# pcb-covox.net
KiCad netlist of a schematic drawn in EAGLE
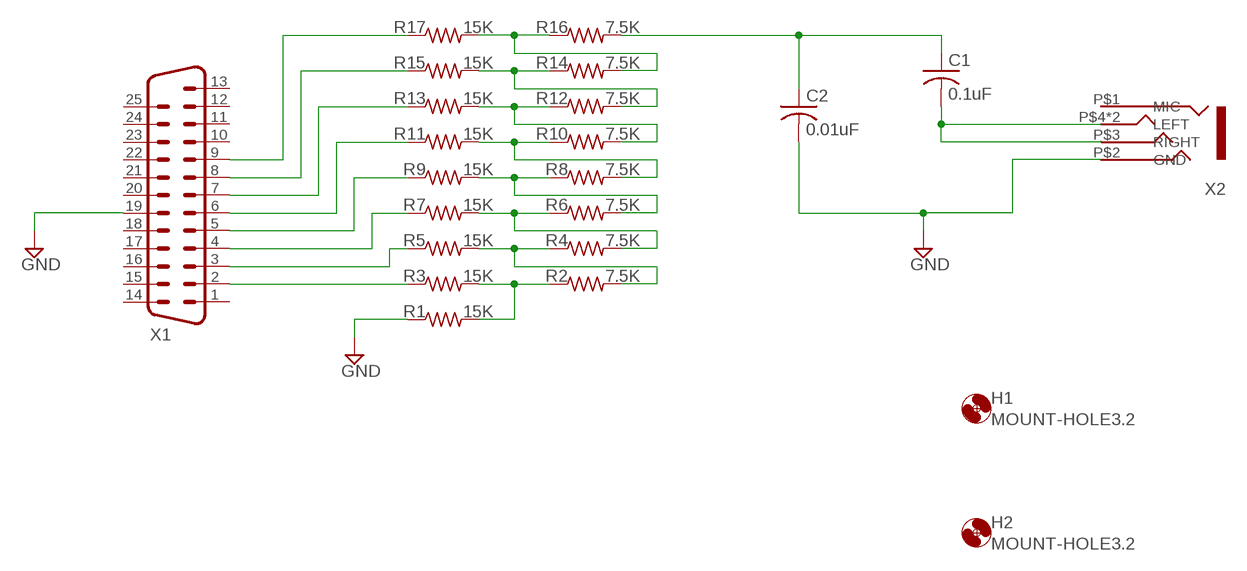
[diagram p0: schematic, sheet 1]

(export (version "E")
  (design (tool "Eeschema 10.0.6"))
  (components
    (comp (ref "C1")
      (value "0.1uF")
      (footprint "eagle-import:C0805")
      (libsource (lib "eagle-import") (part "C-USC0805"))
    )
    (comp (ref "C2")
      (value "0.01uF")
      (footprint "eagle-import:C0805")
      (libsource (lib "eagle-import") (part "C-USC0805"))
    )
    (comp (ref "H1")
      (value "MOUNT-HOLE3.2")
      (footprint "eagle-import:3,2")
      (libsource (lib "eagle-import") (part "MOUNT-HOLE3.2"))
    )
    (comp (ref "H2")
      (value "MOUNT-HOLE3.2")
      (footprint "eagle-import:3,2")
      (libsource (lib "eagle-import") (part "MOUNT-HOLE3.2"))
    )
    (comp (ref "R1")
      (value "15K")
      (footprint "eagle-import:R0805")
      (libsource (lib "eagle-import") (part "R-US_R0805"))
    )
    (comp (ref "R2")
      (value "7.5K")
      (footprint "eagle-import:R0805")
      (libsource (lib "eagle-import") (part "R-US_R0805"))
    )
    (comp (ref "R3")
      (value "15K")
      (footprint "eagle-import:R0805")
      (libsource (lib "eagle-import") (part "R-US_R0805"))
    )
    (comp (ref "R4")
      (value "7.5K")
      (footprint "eagle-import:R0805")
      (libsource (lib "eagle-import") (part "R-US_R0805"))
    )
    (comp (ref "R5")
      (value "15K")
      (footprint "eagle-import:R0805")
      (libsource (lib "eagle-import") (part "R-US_R0805"))
    )
    (comp (ref "R6")
      (value "7.5K")
      (footprint "eagle-import:R0805")
      (libsource (lib "eagle-import") (part "R-US_R0805"))
    )
    (comp (ref "R7")
      (value "15K")
      (footprint "eagle-import:R0805")
      (libsource (lib "eagle-import") (part "R-US_R0805"))
    )
    (comp (ref "R8")
      (value "7.5K")
      (footprint "eagle-import:R0805")
      (libsource (lib "eagle-import") (part "R-US_R0805"))
    )
    (comp (ref "R9")
      (value "15K")
      (footprint "eagle-import:R0805")
      (libsource (lib "eagle-import") (part "R-US_R0805"))
    )
    (comp (ref "R10")
      (value "7.5K")
      (footprint "eagle-import:R0805")
      (libsource (lib "eagle-import") (part "R-US_R0805"))
    )
    (comp (ref "R11")
      (value "15K")
      (footprint "eagle-import:R0805")
      (libsource (lib "eagle-import") (part "R-US_R0805"))
    )
    (comp (ref "R12")
      (value "7.5K")
      (footprint "eagle-import:R0805")
      (libsource (lib "eagle-import") (part "R-US_R0805"))
    )
    (comp (ref "R13")
      (value "15K")
      (footprint "eagle-import:R0805")
      (libsource (lib "eagle-import") (part "R-US_R0805"))
    )
    (comp (ref "R14")
      (value "7.5K")
      (footprint "eagle-import:R0805")
      (libsource (lib "eagle-import") (part "R-US_R0805"))
    )
    (comp (ref "R15")
      (value "15K")
      (footprint "eagle-import:R0805")
      (libsource (lib "eagle-import") (part "R-US_R0805"))
    )
    (comp (ref "R16")
      (value "7.5K")
      (footprint "eagle-import:R0805")
      (libsource (lib "eagle-import") (part "R-US_R0805"))
    )
    (comp (ref "R17")
      (value "15K")
      (footprint "eagle-import:R0805")
      (libsource (lib "eagle-import") (part "R-US_R0805"))
    )
    (comp (ref "X1")
      (value "M25HP")
      (footprint "eagle-import:M25HP")
      (libsource (lib "eagle-import") (part "M25HP"))
    )
    (comp (ref "X2")
      (value "MJ-2135MJ-2135")
      (footprint "eagle-import:MJ-2135")
      (libsource (lib "eagle-import") (part "MJ-2135MJ-2135"))
    )
  )
  (nets
    (net (code "1") (name "GND") (class "Default")
      (node (ref "C2") (pin "2") (pinfunction "2_2") (pintype "passive"))
      (node (ref "R1") (pin "1") (pinfunction "1_1") (pintype "passive"))
      (node (ref "X1") (pin "19") (pinfunction "19_19") (pintype "passive"))
      (node (ref "X2") (pin "P$2") (pinfunction "GND_P$2") (pintype "bidirectional"))
    )
    (net (code "2") (name "Net-(C1-Pad1)") (class "Default")
      (node (ref "C1") (pin "1") (pinfunction "1_1") (pintype "passive"))
      (node (ref "C2") (pin "1") (pinfunction "1_1") (pintype "passive"))
      (node (ref "R16") (pin "2") (pinfunction "2_2") (pintype "passive"))
    )
    (net (code "3") (name "Net-(R1-Pad2)") (class "Default")
      (node (ref "R1") (pin "2") (pinfunction "2_2") (pintype "passive"))
      (node (ref "R2") (pin "1") (pinfunction "1_1") (pintype "passive"))
      (node (ref "R3") (pin "2") (pinfunction "2_2") (pintype "passive"))
    )
    (net (code "4") (name "Net-(R2-Pad2)") (class "Default")
      (node (ref "R2") (pin "2") (pinfunction "2_2") (pintype "passive"))
      (node (ref "R4") (pin "1") (pinfunction "1_1") (pintype "passive"))
      (node (ref "R5") (pin "2") (pinfunction "2_2") (pintype "passive"))
    )
    (net (code "5") (name "Net-(R3-Pad1)") (class "Default")
      (node (ref "R3") (pin "1") (pinfunction "1_1") (pintype "passive"))
      (node (ref "X1") (pin "2") (pinfunction "2_2") (pintype "passive"))
    )
    (net (code "6") (name "Net-(R4-Pad2)") (class "Default")
      (node (ref "R4") (pin "2") (pinfunction "2_2") (pintype "passive"))
      (node (ref "R6") (pin "1") (pinfunction "1_1") (pintype "passive"))
      (node (ref "R7") (pin "2") (pinfunction "2_2") (pintype "passive"))
    )
    (net (code "7") (name "Net-(R5-Pad1)") (class "Default")
      (node (ref "R5") (pin "1") (pinfunction "1_1") (pintype "passive"))
      (node (ref "X1") (pin "3") (pinfunction "3_3") (pintype "passive"))
    )
    (net (code "8") (name "Net-(R6-Pad2)") (class "Default")
      (node (ref "R6") (pin "2") (pinfunction "2_2") (pintype "passive"))
      (node (ref "R8") (pin "1") (pinfunction "1_1") (pintype "passive"))
      (node (ref "R9") (pin "2") (pinfunction "2_2") (pintype "passive"))
    )
    (net (code "9") (name "Net-(R7-Pad1)") (class "Default")
      (node (ref "R7") (pin "1") (pinfunction "1_1") (pintype "passive"))
      (node (ref "X1") (pin "4") (pinfunction "4_4") (pintype "passive"))
    )
    (net (code "10") (name "Net-(R9-Pad1)") (class "Default")
      (node (ref "R9") (pin "1") (pinfunction "1_1") (pintype "passive"))
      (node (ref "X1") (pin "5") (pinfunction "5_5") (pintype "passive"))
    )
    (net (code "11") (name "Net-(R10-Pad1)") (class "Default")
      (node (ref "R10") (pin "1") (pinfunction "1_1") (pintype "passive"))
      (node (ref "R11") (pin "2") (pinfunction "2_2") (pintype "passive"))
      (node (ref "R8") (pin "2") (pinfunction "2_2") (pintype "passive"))
    )
    (net (code "12") (name "Net-(R10-Pad2)") (class "Default")
      (node (ref "R10") (pin "2") (pinfunction "2_2") (pintype "passive"))
      (node (ref "R12") (pin "1") (pinfunction "1_1") (pintype "passive"))
      (node (ref "R13") (pin "2") (pinfunction "2_2") (pintype "passive"))
    )
    (net (code "13") (name "Net-(R11-Pad1)") (class "Default")
      (node (ref "R11") (pin "1") (pinfunction "1_1") (pintype "passive"))
      (node (ref "X1") (pin "6") (pinfunction "6_6") (pintype "passive"))
    )
    (net (code "14") (name "Net-(R12-Pad2)") (class "Default")
      (node (ref "R12") (pin "2") (pinfunction "2_2") (pintype "passive"))
      (node (ref "R14") (pin "1") (pinfunction "1_1") (pintype "passive"))
      (node (ref "R15") (pin "2") (pinfunction "2_2") (pintype "passive"))
    )
    (net (code "15") (name "Net-(R13-Pad1)") (class "Default")
      (node (ref "R13") (pin "1") (pinfunction "1_1") (pintype "passive"))
      (node (ref "X1") (pin "7") (pinfunction "7_7") (pintype "passive"))
    )
    (net (code "16") (name "Net-(R14-Pad2)") (class "Default")
      (node (ref "R14") (pin "2") (pinfunction "2_2") (pintype "passive"))
      (node (ref "R16") (pin "1") (pinfunction "1_1") (pintype "passive"))
      (node (ref "R17") (pin "2") (pinfunction "2_2") (pintype "passive"))
    )
    (net (code "17") (name "Net-(R15-Pad1)") (class "Default")
      (node (ref "R15") (pin "1") (pinfunction "1_1") (pintype "passive"))
      (node (ref "X1") (pin "8") (pinfunction "8_8") (pintype "passive"))
    )
    (net (code "18") (name "Net-(R17-Pad1)") (class "Default")
      (node (ref "R17") (pin "1") (pinfunction "1_1") (pintype "passive"))
      (node (ref "X1") (pin "9") (pinfunction "9_9") (pintype "passive"))
    )
    (net (code "19") (name "Net-(X2-RIGHT)") (class "Default")
      (node (ref "C1") (pin "2") (pinfunction "2_2") (pintype "passive"))
      (node (ref "X2") (pin "P$3") (pinfunction "RIGHT_P$3") (pintype "bidirectional"))
      (node (ref "X2") (pin "P$4") (pinfunction "LEFT_P$4") (pintype "bidirectional"))
      (node (ref "X2") (pin "P$5") (pinfunction "LEFT_P$5") (pintype "bidirectional"))
    )
    (net (code "20") (name "unconnected-(X1-Pad1)") (class "Default")
      (node (ref "X1") (pin "1") (pinfunction "1_1") (pintype "passive"))
    )
    (net (code "21") (name "unconnected-(X1-Pad10)") (class "Default")
      (node (ref "X1") (pin "10") (pinfunction "10_10") (pintype "passive"))
    )
    (net (code "22") (name "unconnected-(X1-Pad11)") (class "Default")
      (node (ref "X1") (pin "11") (pinfunction "11_11") (pintype "passive"))
    )
    (net (code "23") (name "unconnected-(X1-Pad12)") (class "Default")
      (node (ref "X1") (pin "12") (pinfunction "12_12") (pintype "passive"))
    )
    (net (code "24") (name "unconnected-(X1-Pad13)") (class "Default")
      (node (ref "X1") (pin "13") (pinfunction "13_13") (pintype "passive"))
    )
    (net (code "25") (name "unconnected-(X1-Pad14)") (class "Default")
      (node (ref "X1") (pin "14") (pinfunction "14_14") (pintype "passive"))
    )
    (net (code "26") (name "unconnected-(X1-Pad15)") (class "Default")
      (node (ref "X1") (pin "15") (pinfunction "15_15") (pintype "passive"))
    )
    (net (code "27") (name "unconnected-(X1-Pad16)") (class "Default")
      (node (ref "X1") (pin "16") (pinfunction "16_16") (pintype "passive"))
    )
    (net (code "28") (name "unconnected-(X1-Pad17)") (class "Default")
      (node (ref "X1") (pin "17") (pinfunction "17_17") (pintype "passive"))
    )
    (net (code "29") (name "unconnected-(X1-Pad18)") (class "Default")
      (node (ref "X1") (pin "18") (pinfunction "18_18") (pintype "passive"))
    )
    (net (code "30") (name "unconnected-(X1-Pad20)") (class "Default")
      (node (ref "X1") (pin "20") (pinfunction "20_20") (pintype "passive"))
    )
    (net (code "31") (name "unconnected-(X1-Pad21)") (class "Default")
      (node (ref "X1") (pin "21") (pinfunction "21_21") (pintype "passive"))
    )
    (net (code "32") (name "unconnected-(X1-Pad22)") (class "Default")
      (node (ref "X1") (pin "22") (pinfunction "22_22") (pintype "passive"))
    )
    (net (code "33") (name "unconnected-(X1-Pad23)") (class "Default")
      (node (ref "X1") (pin "23") (pinfunction "23_23") (pintype "passive"))
    )
    (net (code "34") (name "unconnected-(X1-Pad24)") (class "Default")
      (node (ref "X1") (pin "24") (pinfunction "24_24") (pintype "passive"))
    )
    (net (code "35") (name "unconnected-(X1-Pad25)") (class "Default")
      (node (ref "X1") (pin "25") (pinfunction "25_25") (pintype "passive"))
    )
    (net (code "36") (name "unconnected-(X2-MIC-PadP$1)") (class "Default")
      (node (ref "X2") (pin "P$1") (pinfunction "MIC_P$1") (pintype "bidirectional"))
    )
  )
)
